# Connectors.net
KiCad netlist of a schematic drawn in Altium Designer
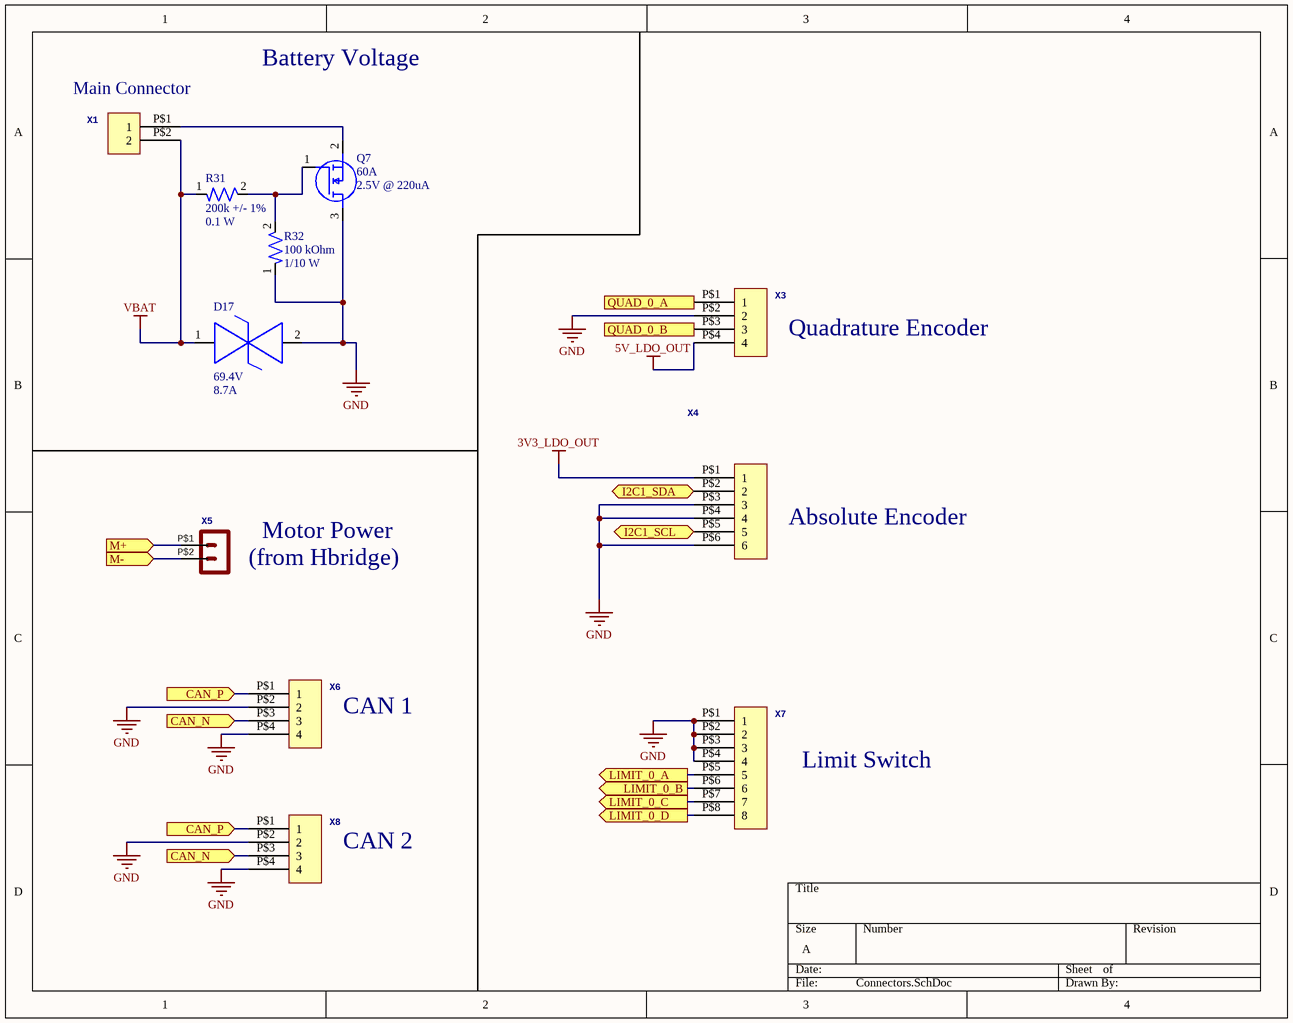
[diagram p0: Connectors.SchDoc]

(export (version "E")
  (design (tool "Eeschema 10.0.6"))
  (components
    (comp (ref "D17")
      (value "SMBJE43CAH")
      (footprint "DO-214AA (SMBJ)")
      (description "69.4V Clamp 8.7A Ipp Tvs Diode Surface Mount DO-214AA (SMBJ)")
      (fields (field (name "VCLAMP") "69.4V") (field (name "PEAK PULSER CURRENT") "8.7A"))
      (libsource (lib "MasterLib") (part "DIO-69.4V-0001"))
    )
    (comp (ref "Q7")
      (value "TPH7R006PL,L1Q")
      (footprint "NMOS-8PowerVDFN")
      (description "N-Channel 60 V 60A (Tc) 81W (Tc) Surface Mount 8-SOP Advance (5x5)")
      (fields (field (name "DRAIN CURRENT") "60A") (field (name "VGS") "2.5V @ 220uA"))
      (libsource (lib "MasterLib") (part "NMOS-60A-0001"))
    )
    (comp (ref "R31")
      (value "ERJ-3EKF2003V")
      (footprint "RES-0603")
      (description "200 kOhms ±1% 0.1W, 1/10W Chip Resistor 0603 (1608 Metric) Automotive AEC-Q200 Thick Film")
      (fields
        (field (name "MANUFACTURER") "Panasonic Electronic Components")
        (field (name "RESISTANCE") "200k +/- 1%")
        (field (name "POWER RATING") "0.1 W")
      )
      (libsource (lib "MasterLib") (part "RES-200K-0001"))
    )
    (comp (ref "R32")
      (value "RC0603FR-07100KL")
      (footprint "RES-0603")
      (description "100 kOhms ±1% 0.1W, 1/10W Chip Resistor 0603 (1608 Metric) Moisture Resistant Thick Film")
      (fields
        (field (name "TOLERANCE") "+/- 1%")
        (field (name "RESISTANCE") "100 kOhm")
        (field (name "POWER") "1/10 W")
      )
      (libsource (lib "MasterLib") (part "RES-100K-0003"))
    )
    (comp (ref "X1")
      (value "Molex 43650-0215")
      (footprint "43650-0215")
      (libsource (lib "Molex Microfit") (part "Micro-Fit Molex 2 Pin Vertical"))
    )
    (comp (ref "X3")
      (value "Molex 43045-0412")
      (footprint "43045-0412")
      (libsource (lib "Molex Microfit") (part "Micro-Fit Molex 4 Pin 2 Row Vertical"))
    )
    (comp (ref "X4")
      (value "Molex 43045-0612")
      (footprint "43045-0612")
      (libsource (lib "Molex Microfit") (part "Micro-Fit Molex 6 Pin 2 Row Vertical"))
    )
    (comp (ref "X5")
      (value "Molex - Micro-Fit 3.0 Series connector,  3.00mm (0.118\") pitch header, 2 positions.")
      (footprint "43045-0212")
      (libsource (lib "Molex Microfit") (part "HEADER_POS2_?43045-0212"))
    )
    (comp (ref "X6")
      (value "Molex 43045-0412")
      (footprint "43045-0412")
      (libsource (lib "Molex Microfit") (part "Micro-Fit Molex 4 Pin 2 Row Vertical"))
    )
    (comp (ref "X7")
      (value "Molex 43045-0812")
      (footprint "43045-0812")
      (libsource (lib "Molex Microfit") (part "Micro-Fit Molex 8 Pin 2 Row Vertical"))
    )
    (comp (ref "X8")
      (value "Molex 43045-0412")
      (footprint "43045-0412")
      (libsource (lib "Molex Microfit") (part "Micro-Fit Molex 4 Pin 2 Row Vertical"))
    )
  )
  (nets
    (net (code "1") (name "/CAN_N") (class "Default")
      (node (ref "X6") (pin "P$3") (pinfunction "3_P$3") (pintype "passive"))
      (node (ref "X8") (pin "P$3") (pinfunction "3_P$3") (pintype "passive"))
    )
    (net (code "2") (name "/CAN_P") (class "Default")
      (node (ref "X6") (pin "P$1") (pinfunction "1_P$1") (pintype "passive"))
      (node (ref "X8") (pin "P$1") (pinfunction "1_P$1") (pintype "passive"))
    )
    (net (code "3") (name "/I2C1_SCL") (class "Default")
      (node (ref "X4") (pin "P$5") (pinfunction "5_P$5") (pintype "passive"))
    )
    (net (code "4") (name "/I2C1_SDA") (class "Default")
      (node (ref "X4") (pin "P$2") (pinfunction "2_P$2") (pintype "passive"))
    )
    (net (code "5") (name "/LIMIT_0_A") (class "Default")
      (node (ref "X7") (pin "P$5") (pinfunction "5_P$5") (pintype "passive"))
    )
    (net (code "6") (name "/LIMIT_0_B") (class "Default")
      (node (ref "X7") (pin "P$6") (pinfunction "6_P$6") (pintype "passive"))
    )
    (net (code "7") (name "/LIMIT_0_C") (class "Default")
      (node (ref "X7") (pin "P$7") (pinfunction "7_P$7") (pintype "passive"))
    )
    (net (code "8") (name "/LIMIT_0_D") (class "Default")
      (node (ref "X7") (pin "P$8") (pinfunction "8_P$8") (pintype "passive"))
    )
    (net (code "9") (name "/M+") (class "Default")
      (node (ref "X5") (pin "P$1") (pinfunction "1_P$1") (pintype "passive"))
    )
    (net (code "10") (name "/M-") (class "Default")
      (node (ref "X5") (pin "P$2") (pinfunction "2_P$2") (pintype "passive"))
    )
    (net (code "11") (name "/QUAD_0_A") (class "Default")
      (node (ref "X3") (pin "P$1") (pinfunction "1_P$1") (pintype "passive"))
    )
    (net (code "12") (name "/QUAD_0_B") (class "Default")
      (node (ref "X3") (pin "P$3") (pinfunction "3_P$3") (pintype "passive"))
    )
    (net (code "13") (name "3V3_LDO_OUT") (class "Default")
      (node (ref "X4") (pin "P$1") (pinfunction "1_P$1") (pintype "passive"))
    )
    (net (code "14") (name "5V_LDO_OUT") (class "Default")
      (node (ref "X3") (pin "P$4") (pinfunction "4_P$4") (pintype "passive"))
    )
    (net (code "15") (name "GND") (class "Default")
      (node (ref "D17") (pin "2") (pintype "passive"))
      (node (ref "Q7") (pin "3") (pinfunction "D_3") (pintype "passive"))
      (node (ref "R32") (pin "1") (pinfunction "1_1") (pintype "passive"))
      (node (ref "X3") (pin "P$2") (pinfunction "2_P$2") (pintype "passive"))
      (node (ref "X4") (pin "P$3") (pinfunction "3_P$3") (pintype "passive"))
      (node (ref "X4") (pin "P$4") (pinfunction "4_P$4") (pintype "passive"))
      (node (ref "X4") (pin "P$6") (pinfunction "6_P$6") (pintype "passive"))
      (node (ref "X6") (pin "P$2") (pinfunction "2_P$2") (pintype "passive"))
      (node (ref "X6") (pin "P$4") (pinfunction "4_P$4") (pintype "passive"))
      (node (ref "X7") (pin "P$1") (pinfunction "1_P$1") (pintype "passive"))
      (node (ref "X7") (pin "P$2") (pinfunction "2_P$2") (pintype "passive"))
      (node (ref "X7") (pin "P$3") (pinfunction "3_P$3") (pintype "passive"))
      (node (ref "X7") (pin "P$4") (pinfunction "4_P$4") (pintype "passive"))
      (node (ref "X8") (pin "P$2") (pinfunction "2_P$2") (pintype "passive"))
      (node (ref "X8") (pin "P$4") (pinfunction "4_P$4") (pintype "passive"))
    )
    (net (code "16") (name "Net-(Q7-G)") (class "Default")
      (node (ref "Q7") (pin "1") (pinfunction "G_1") (pintype "passive"))
      (node (ref "R31") (pin "2") (pinfunction "2_2") (pintype "passive"))
      (node (ref "R32") (pin "2") (pinfunction "2_2") (pintype "passive"))
    )
    (net (code "17") (name "Net-(Q7-S)") (class "Default")
      (node (ref "Q7") (pin "2") (pinfunction "S_2") (pintype "passive"))
      (node (ref "X1") (pin "P$1") (pinfunction "1_P$1") (pintype "passive"))
    )
    (net (code "18") (name "VBAT") (class "Default")
      (node (ref "D17") (pin "1") (pintype "passive"))
      (node (ref "R31") (pin "1") (pinfunction "1_1") (pintype "passive"))
      (node (ref "X1") (pin "P$2") (pinfunction "2_P$2") (pintype "passive"))
    )
  )
)
